# tablo_tara2.net
KiCad netlist of a schematic drawn in Altium Designer
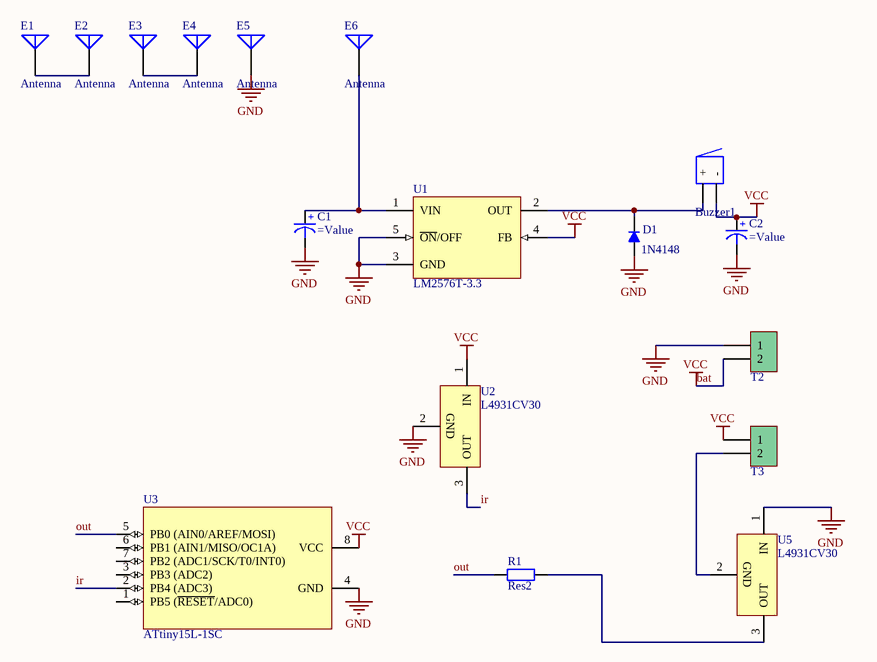
[diagram p0: tablo tara2.SchDoc]

(export (version "E")
  (design (tool "Eeschema 10.0.6"))
  (components
    (comp (ref "Buzzer1")
      (value "Buzzer")
      (footprint "BUZZER")
      (fields (field (name "DESIGNER") "Seyed Mohsen Ghasemain"))
      (libsource (lib "PicPars.com_usefully_Library") (part "Buzzer"))
    )
    (comp (ref "C1")
      (value "~")
      (footprint "ELEC-CAP-RAD10-20")
      (description "Electrolytic Capacitor")
      (libsource (lib "AltiumLib1") (part "Capacitor Electrolytic"))
    )
    (comp (ref "C2")
      (value "~")
      (footprint "ELEC-CAP-RAD10-20")
      (description "Electrolytic Capacitor")
      (libsource (lib "AltiumLib1") (part "Capacitor Electrolytic"))
    )
    (comp (ref "D1")
      (value "MODEL")
      (footprint "DO-41")
      (description "Diode")
      (fields (field (name "MODEL") "1N4148"))
      (libsource (lib "AltiumLib1") (part "Diode"))
    )
    (comp (ref "E1")
      (value "Antenna")
      (footprint "PIN1")
      (description "Generic Antenna")
      (fields (field (name "PUBLISHER") "Altium Limited"))
      (libsource (lib "Miscellaneous Devices") (part "Antenna"))
    )
    (comp (ref "E2")
      (value "Antenna")
      (footprint "PIN1")
      (description "Generic Antenna")
      (fields (field (name "PUBLISHER") "Altium Limited"))
      (libsource (lib "Miscellaneous Devices") (part "Antenna"))
    )
    (comp (ref "E3")
      (value "Antenna")
      (footprint "PIN1")
      (description "Generic Antenna")
      (fields (field (name "PUBLISHER") "Altium Limited"))
      (libsource (lib "Miscellaneous Devices") (part "Antenna"))
    )
    (comp (ref "E4")
      (value "Antenna")
      (footprint "PIN1")
      (description "Generic Antenna")
      (fields (field (name "PUBLISHER") "Altium Limited"))
      (libsource (lib "Miscellaneous Devices") (part "Antenna"))
    )
    (comp (ref "E5")
      (value "Antenna")
      (footprint "PIN1")
      (description "Generic Antenna")
      (fields (field (name "PUBLISHER") "Altium Limited"))
      (libsource (lib "Miscellaneous Devices") (part "Antenna"))
    )
    (comp (ref "E6")
      (value "Antenna")
      (footprint "PIN1")
      (description "Generic Antenna")
      (fields (field (name "PUBLISHER") "Altium Limited"))
      (libsource (lib "Miscellaneous Devices") (part "Antenna"))
    )
    (comp (ref "R1")
      (value "Res2")
      (footprint "Res50")
      (description "Resistor")
      (fields (field (name "PUBLISHER") "Altium Limited"))
      (libsource (lib "Miscellaneous Devices") (part "Res50"))
    )
    (comp (ref "T2")
      (value "Phoenix terminal")
      (footprint "phoenix terminal 2")
      (description "Terminal 2 Pin")
      (fields (field (name "DESIGNER") "Seyed Mohsen Ghasemain") (field (name "E-MAIL") "picpars@gmail.com"))
      (libsource (lib "PicPars.com_usefully_Library") (part "Phoenix terminal 2"))
    )
    (comp (ref "T3")
      (value "Phoenix terminal")
      (footprint "phoenix terminal 2")
      (description "Terminal 2 Pin")
      (fields (field (name "DESIGNER") "Seyed Mohsen Ghasemain") (field (name "E-MAIL") "picpars@gmail.com"))
      (libsource (lib "PicPars.com_usefully_Library") (part "Phoenix terminal 2"))
    )
    (comp (ref "U1")
      (value "LM2576T-3.3")
      (footprint "T05A")
      (description "SIMPLE SWITCHER; 3A Step-Down Voltage Regulator")
      (fields
        (field (name "MANUFACTURER") "National Semiconductor")
        (field (name "DIGIKEYPARTNUMBER") "LM2576T-3.3NS-ND")
        (field (name "PUBLISHER") "Altium Limited")
      )
      (libsource (lib "NSC Switcher") (part "LM2576T-3.3"))
    )
    (comp (ref "U2")
      (value "L4931CV30")
      (footprint "TO-220A")
      (description "250mA, Very Low Drop ( 0.4V) Voltage Regulator")
      (fields (field (name "PUBLISHER") "Altium Limited"))
      (libsource (lib "ST Power Mgt Voltage Regulator") (part "L4931CV30"))
    )
    (comp (ref "U3")
      (value "ATtiny15L-1SC")
      (footprint "8S2_N")
      (description "8-Bit AVR Microcontroller with 1K Byte of Flash Memory")
      (fields (field (name "PUBLISHER") "Altium Limited"))
      (libsource (lib "Atmel Microcontroller 8-Bit AVR") (part "ATtiny15L-1SC"))
    )
    (comp (ref "U5")
      (value "L4931CV30")
      (footprint "TO-220A")
      (description "250mA, Very Low Drop ( 0.4V) Voltage Regulator")
      (fields (field (name "PUBLISHER") "Altium Limited"))
      (libsource (lib "ST Power Mgt Voltage Regulator") (part "L4931CV30"))
    )
  )
  (nets
    (net (code "1") (name "/ir") (class "Default")
      (node (ref "U2") (pin "3") (pinfunction "OUT_3") (pintype "power_in"))
      (node (ref "U3") (pin "2") (pinfunction "PB4_(ADC3)_2") (pintype "bidirectional"))
    )
    (net (code "2") (name "/out") (class "Default")
      (node (ref "R1") (pin "1") (pinfunction "1_1") (pintype "passive"))
      (node (ref "U3") (pin "5") (pinfunction "PB0_(AIN0/AREF/MOSI)_5") (pintype "bidirectional"))
    )
    (net (code "3") (name "GND") (class "Default")
      (node (ref "C1") (pin "1") (pinfunction "-_1") (pintype "passive"))
      (node (ref "C2") (pin "1") (pinfunction "-_1") (pintype "passive"))
      (node (ref "D1") (pin "1") (pinfunction "A_1") (pintype "passive"))
      (node (ref "E5") (pin "1") (pinfunction "A_1") (pintype "passive"))
      (node (ref "T2") (pin "1") (pinfunction "1_1") (pintype "passive"))
      (node (ref "U1") (pin "3") (pinfunction "GND_3") (pintype "power_in"))
      (node (ref "U1") (pin "5") (pinfunction "~{ON}/OFF_5") (pintype "input"))
      (node (ref "U2") (pin "2") (pinfunction "GND_2") (pintype "power_in"))
      (node (ref "U3") (pin "4") (pinfunction "GND_4") (pintype "power_in"))
      (node (ref "U5") (pin "1") (pinfunction "IN_1") (pintype "power_in"))
    )
    (net (code "4") (name "Net-(Buzzer1-+)") (class "Default")
      (node (ref "Buzzer1") (pin "1") (pinfunction "+_1") (pintype "passive"))
      (node (ref "D1") (pin "2") (pinfunction "K_2") (pintype "passive"))
      (node (ref "U1") (pin "2") (pinfunction "OUT_2") (pintype "power_in"))
    )
    (net (code "5") (name "Net-(C1-+)") (class "Default")
      (node (ref "C1") (pin "2") (pinfunction "+_2") (pintype "passive"))
      (node (ref "E6") (pin "1") (pinfunction "A_1") (pintype "passive"))
      (node (ref "U1") (pin "1") (pinfunction "VIN_1") (pintype "power_in"))
    )
    (net (code "6") (name "Net-(E1-A)") (class "Default")
      (node (ref "E1") (pin "1") (pinfunction "A_1") (pintype "passive"))
      (node (ref "E2") (pin "1") (pinfunction "A_1") (pintype "passive"))
    )
    (net (code "7") (name "Net-(E3-A)") (class "Default")
      (node (ref "E3") (pin "1") (pinfunction "A_1") (pintype "passive"))
      (node (ref "E4") (pin "1") (pinfunction "A_1") (pintype "passive"))
    )
    (net (code "8") (name "Net-(U5-GND)") (class "Default")
      (node (ref "T3") (pin "2") (pinfunction "2_2") (pintype "passive"))
      (node (ref "U5") (pin "2") (pinfunction "GND_2") (pintype "power_in"))
    )
    (net (code "9") (name "Net-(U5-OUT)") (class "Default")
      (node (ref "R1") (pin "2") (pinfunction "2_2") (pintype "passive"))
      (node (ref "U5") (pin "3") (pinfunction "OUT_3") (pintype "power_in"))
    )
    (net (code "10") (name "VCC") (class "Default")
      (node (ref "Buzzer1") (pin "2") (pinfunction "-_2") (pintype "passive"))
      (node (ref "C2") (pin "2") (pinfunction "+_2") (pintype "passive"))
      (node (ref "T2") (pin "2") (pinfunction "2_2") (pintype "passive"))
      (node (ref "T3") (pin "1") (pinfunction "1_1") (pintype "passive"))
      (node (ref "U1") (pin "4") (pinfunction "FB_4") (pintype "input"))
      (node (ref "U2") (pin "1") (pinfunction "IN_1") (pintype "power_in"))
      (node (ref "U3") (pin "8") (pinfunction "VCC_8") (pintype "power_in"))
    )
    (net (code "11") (name "unconnected-(U3-PB1_(AIN1{slash}MISO{slash}OC1A)-Pad6)") (class "Default")
      (node (ref "U3") (pin "6") (pinfunction "PB1_(AIN1/MISO/OC1A)_6") (pintype "bidirectional"))
    )
    (net (code "12") (name "unconnected-(U3-PB2_(ADC1{slash}SCK{slash}T0{slash}INT0)-Pad7)") (class "Default")
      (node (ref "U3") (pin "7") (pinfunction "PB2_(ADC1/SCK/T0/INT0)_7") (pintype "bidirectional"))
    )
    (net (code "13") (name "unconnected-(U3-PB3_(ADC2)-Pad3)") (class "Default")
      (node (ref "U3") (pin "3") (pinfunction "PB3_(ADC2)_3") (pintype "bidirectional"))
    )
    (net (code "14") (name "unconnected-(U3-PB5_(~{RESET}{slash}ADC0)-Pad1)") (class "Default")
      (node (ref "U3") (pin "1") (pinfunction "PB5_(~{RESET}/ADC0)_1") (pintype "bidirectional"))
    )
  )
)
